# 03-DRAM_Memory.net
KiCad netlist of a schematic drawn in Altium Designer
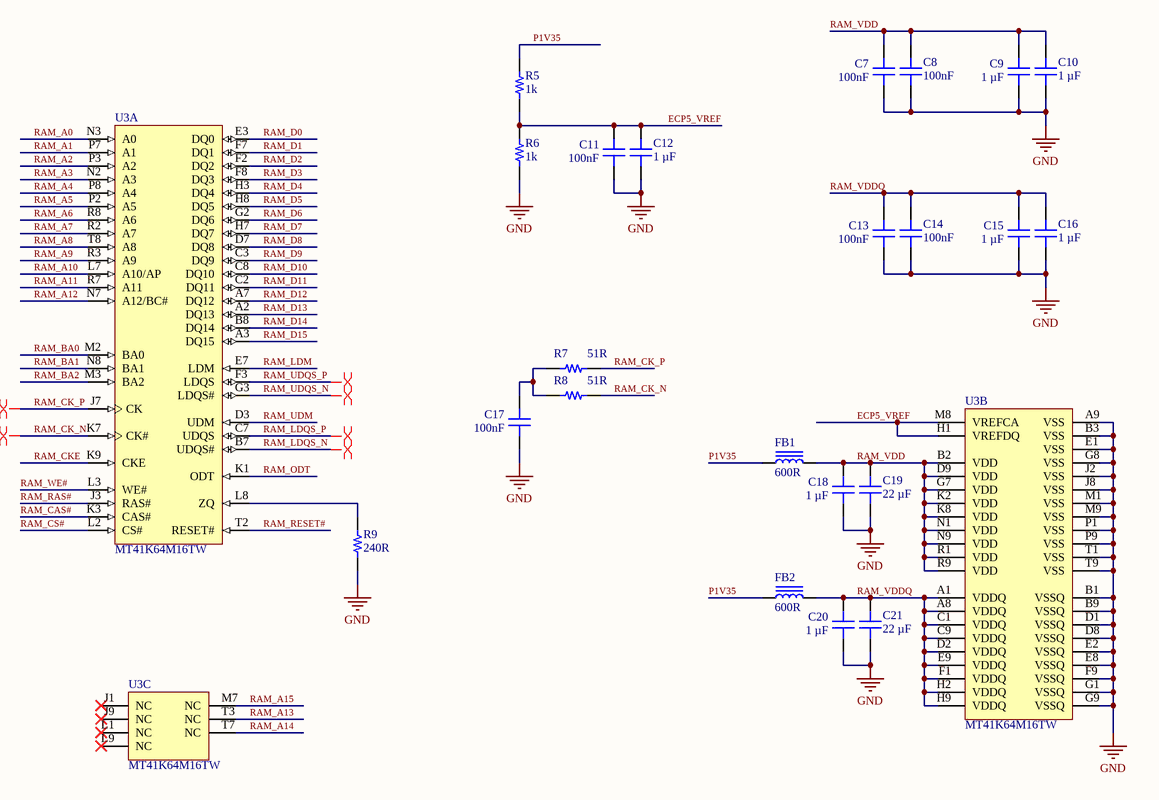
[diagram p0: 03-DRAM_Memory.SchDoc]

(export (version "E")
  (design (tool "Eeschema 10.0.6"))
  (components
    (comp (ref "C7")
      (value "100nF")
      (footprint "CAP 0201_0603")
      (description "CAP CER 0.1UF 6.3V X6S 0201")
      (fields
        (field (name "PART NUMBER") "GRT033C80J104KE01J")
        (field (name "MANUFACTURER") "Murata Electronics")
        (field (name "LASTUPDATED") "3/01/2023 8:00:58 p. m.")
      )
      (libsource (lib "Celestial Altium Library - altium_library") (part "Capacitor"))
    )
    (comp (ref "C8")
      (value "100nF")
      (footprint "CAP 0201_0603")
      (description "CAP CER 0.1UF 6.3V X6S 0201")
      (fields
        (field (name "PART NUMBER") "GRT033C80J104KE01J")
        (field (name "MANUFACTURER") "Murata Electronics")
        (field (name "LASTUPDATED") "3/01/2023 8:00:58 p. m.")
      )
      (libsource (lib "Celestial Altium Library - altium_library") (part "Capacitor"))
    )
    (comp (ref "C9")
      (value "1 µF")
      (footprint "CAP 0402_1005")
      (description "CAP CER 1UF 10V X6S 0402")
      (fields
        (field (name "PART NUMBER") "LMK105C6105KV-F")
        (field (name "MANUFACTURER") "Taiyo Yuden")
        (field (name "LASTUPDATED") "3/01/2023 8:04:17 p. m.")
      )
      (libsource (lib "Celestial Altium Library - altium_library") (part "Capacitor"))
    )
    (comp (ref "C10")
      (value "1 µF")
      (footprint "CAP 0402_1005")
      (description "CAP CER 1UF 10V X6S 0402")
      (fields
        (field (name "PART NUMBER") "LMK105C6105KV-F")
        (field (name "MANUFACTURER") "Taiyo Yuden")
        (field (name "LASTUPDATED") "3/01/2023 8:04:17 p. m.")
      )
      (libsource (lib "Celestial Altium Library - altium_library") (part "Capacitor"))
    )
    (comp (ref "C11")
      (value "100nF")
      (footprint "CAP 0201_0603")
      (description "CAP CER 0.1UF 6.3V X6S 0201")
      (fields
        (field (name "PART NUMBER") "GRT033C80J104KE01J")
        (field (name "MANUFACTURER") "Murata Electronics")
        (field (name "LASTUPDATED") "3/01/2023 8:00:58 p. m.")
      )
      (libsource (lib "Celestial Altium Library - altium_library") (part "Capacitor"))
    )
    (comp (ref "C12")
      (value "1 µF")
      (footprint "CAP 0402_1005")
      (description "CAP CER 1UF 10V X6S 0402")
      (fields
        (field (name "PART NUMBER") "LMK105C6105KV-F")
        (field (name "MANUFACTURER") "Taiyo Yuden")
        (field (name "LASTUPDATED") "3/01/2023 8:04:17 p. m.")
      )
      (libsource (lib "Celestial Altium Library - altium_library") (part "Capacitor"))
    )
    (comp (ref "C13")
      (value "100nF")
      (footprint "CAP 0201_0603")
      (description "CAP CER 0.1UF 6.3V X6S 0201")
      (fields
        (field (name "PART NUMBER") "GRT033C80J104KE01J")
        (field (name "MANUFACTURER") "Murata Electronics")
        (field (name "LASTUPDATED") "3/01/2023 8:00:58 p. m.")
      )
      (libsource (lib "Celestial Altium Library - altium_library") (part "Capacitor"))
    )
    (comp (ref "C14")
      (value "100nF")
      (footprint "CAP 0201_0603")
      (description "CAP CER 0.1UF 6.3V X6S 0201")
      (fields
        (field (name "PART NUMBER") "GRT033C80J104KE01J")
        (field (name "MANUFACTURER") "Murata Electronics")
        (field (name "LASTUPDATED") "3/01/2023 8:00:58 p. m.")
      )
      (libsource (lib "Celestial Altium Library - altium_library") (part "Capacitor"))
    )
    (comp (ref "C15")
      (value "1 µF")
      (footprint "CAP 0402_1005")
      (description "CAP CER 1UF 10V X6S 0402")
      (fields
        (field (name "PART NUMBER") "LMK105C6105KV-F")
        (field (name "MANUFACTURER") "Taiyo Yuden")
        (field (name "LASTUPDATED") "3/01/2023 8:04:17 p. m.")
      )
      (libsource (lib "Celestial Altium Library - altium_library") (part "Capacitor"))
    )
    (comp (ref "C16")
      (value "1 µF")
      (footprint "CAP 0402_1005")
      (description "CAP CER 1UF 10V X6S 0402")
      (fields
        (field (name "PART NUMBER") "LMK105C6105KV-F")
        (field (name "MANUFACTURER") "Taiyo Yuden")
        (field (name "LASTUPDATED") "3/01/2023 8:04:17 p. m.")
      )
      (libsource (lib "Celestial Altium Library - altium_library") (part "Capacitor"))
    )
    (comp (ref "C17")
      (value "100nF")
      (footprint "CAP 0201_0603")
      (description "CAP CER 0.1UF 6.3V X6S 0201")
      (fields
        (field (name "PART NUMBER") "GRT033C80J104KE01J")
        (field (name "MANUFACTURER") "Murata Electronics")
        (field (name "LASTUPDATED") "3/01/2023 8:00:58 p. m.")
      )
      (libsource (lib "Celestial Altium Library - altium_library") (part "Capacitor"))
    )
    (comp (ref "C18")
      (value "1 µF")
      (footprint "CAP 0402_1005")
      (description "CAP CER 1UF 10V X6S 0402")
      (fields
        (field (name "PART NUMBER") "LMK105C6105KV-F")
        (field (name "MANUFACTURER") "Taiyo Yuden")
        (field (name "LASTUPDATED") "3/01/2023 8:04:17 p. m.")
      )
      (libsource (lib "Celestial Altium Library - altium_library") (part "Capacitor"))
    )
    (comp (ref "C19")
      (value "22 µF")
      (footprint "CAP 0603_1608")
      (description "CAP CER 22UF 6.3V X5R 0603")
      (fields
        (field (name "PART NUMBER") "GRM186R60J226ME15D")
        (field (name "MANUFACTURER") "Murata Electronics")
        (field (name "LASTUPDATED") "3/01/2023 8:07:48 p. m.")
      )
      (libsource (lib "Celestial Altium Library - altium_library") (part "Capacitor"))
    )
    (comp (ref "C20")
      (value "1 µF")
      (footprint "CAP 0402_1005")
      (description "CAP CER 1UF 10V X6S 0402")
      (fields
        (field (name "PART NUMBER") "LMK105C6105KV-F")
        (field (name "MANUFACTURER") "Taiyo Yuden")
        (field (name "LASTUPDATED") "3/01/2023 8:04:17 p. m.")
      )
      (libsource (lib "Celestial Altium Library - altium_library") (part "Capacitor"))
    )
    (comp (ref "C21")
      (value "22 µF")
      (footprint "CAP 0603_1608")
      (description "CAP CER 22UF 6.3V X5R 0603")
      (fields
        (field (name "PART NUMBER") "GRM186R60J226ME15D")
        (field (name "MANUFACTURER") "Murata Electronics")
        (field (name "LASTUPDATED") "3/01/2023 8:07:48 p. m.")
      )
      (libsource (lib "Celestial Altium Library - altium_library") (part "Capacitor"))
    )
    (comp (ref "FB1")
      (value "600R")
      (footprint "IND 0402_1005 RF WW")
      (description "FIXED IND 4.8NH 1.2A 71MOHM SMD")
      (fields
        (field (name "PART NUMBER") "LQW15AN4N8D8ZD")
        (field (name "MANUFACTURER") "Murata Electronics")
        (field (name "LASTUPDATED") "2/01/2023 8:59:34 p. m.")
      )
      (libsource (lib "Celestial Altium Library - altium_library") (part "Inductor"))
    )
    (comp (ref "FB2")
      (value "600R")
      (footprint "IND 0402_1005 RF WW")
      (description "FIXED IND 4.8NH 1.2A 71MOHM SMD")
      (fields
        (field (name "PART NUMBER") "LQW15AN4N8D8ZD")
        (field (name "MANUFACTURER") "Murata Electronics")
        (field (name "LASTUPDATED") "2/01/2023 8:59:34 p. m.")
      )
      (libsource (lib "Celestial Altium Library - altium_library") (part "Inductor"))
    )
    (comp (ref "R5")
      (value "1k")
      (footprint "RES 0201_0603")
      (description "RES SMD 10K OHM 0.1% 1/20W 0201")
      (fields
        (field (name "PART NUMBER") "ERA-1AEB103C")
        (field (name "MANUFACTURER") "Panasonic Electronic Components")
        (field (name "LASTUPDATED") "3/01/2023 8:15:23 p. m.")
      )
      (libsource (lib "Celestial Altium Library - altium_library") (part "Resistor"))
    )
    (comp (ref "R6")
      (value "1k")
      (footprint "RES 0201_0603")
      (description "RES SMD 10K OHM 0.1% 1/20W 0201")
      (fields
        (field (name "PART NUMBER") "ERA-1AEB103C")
        (field (name "MANUFACTURER") "Panasonic Electronic Components")
        (field (name "LASTUPDATED") "3/01/2023 8:15:23 p. m.")
      )
      (libsource (lib "Celestial Altium Library - altium_library") (part "Resistor"))
    )
    (comp (ref "R7")
      (value "51R")
      (footprint "RES 0201_0603")
      (description "RES SMD 10K OHM 0.1% 1/20W 0201")
      (fields
        (field (name "PART NUMBER") "ERA-1AEB103C")
        (field (name "MANUFACTURER") "Panasonic Electronic Components")
        (field (name "LASTUPDATED") "3/01/2023 8:15:23 p. m.")
      )
      (libsource (lib "Celestial Altium Library - altium_library") (part "Resistor"))
    )
    (comp (ref "R8")
      (value "51R")
      (footprint "RES 0201_0603")
      (description "RES SMD 10K OHM 0.1% 1/20W 0201")
      (fields
        (field (name "PART NUMBER") "ERA-1AEB103C")
        (field (name "MANUFACTURER") "Panasonic Electronic Components")
        (field (name "LASTUPDATED") "3/01/2023 8:15:23 p. m.")
      )
      (libsource (lib "Celestial Altium Library - altium_library") (part "Resistor"))
    )
    (comp (ref "R9")
      (value "240R")
      (footprint "RES 0402_1005")
      (description "RES SMD 124 OHM 1% 1/10W 0402")
      (fields
        (field (name "PART NUMBER") "ERJ-2RKF1240X")
        (field (name "MANUFACTURER") "Panasonic Electronic Components")
        (field (name "LASTUPDATED") "2/01/2023 8:21:47 p. m.")
      )
      (libsource (lib "Celestial Altium Library - altium_library") (part "Resistor"))
    )
    (comp (ref "U3")
      (value "MT41K64M16TW")
      (footprint "MICT-TW-96")
      (description "DDR3L SDRAM, 8 Meg x 16 x 8 Bank, 1.07 ns, 0 to 95 degC, 96-Ball FBGA (TW), Pb-Free")
      (libsource (lib "MT41K64M16TW") (part "MT41K64M16TW"))
    )
  )
  (nets
    (net (code "1") (name "/ECP5_VREF") (class "Default")
      (node (ref "C11") (pin "2") (pinfunction "2_2") (pintype "passive"))
      (node (ref "C12") (pin "2") (pinfunction "2_2") (pintype "passive"))
      (node (ref "R5") (pin "2") (pinfunction "2_2") (pintype "passive"))
      (node (ref "R6") (pin "1") (pinfunction "1_1") (pintype "passive"))
      (node (ref "U3") (pin "H1") (pinfunction "VREFDQ_H1") (pintype "power_in"))
      (node (ref "U3") (pin "M8") (pinfunction "VREFCA_M8") (pintype "power_in"))
    )
    (net (code "2") (name "/P1V35") (class "Default")
      (node (ref "FB1") (pin "1") (pinfunction "1_1") (pintype "passive"))
      (node (ref "FB2") (pin "1") (pinfunction "1_1") (pintype "passive"))
      (node (ref "R5") (pin "1") (pinfunction "1_1") (pintype "passive"))
    )
    (net (code "3") (name "/RAM_A0") (class "Default")
      (node (ref "U3") (pin "N3") (pinfunction "A0_N3") (pintype "input"))
    )
    (net (code "4") (name "/RAM_A1") (class "Default")
      (node (ref "U3") (pin "P7") (pinfunction "A1_P7") (pintype "input"))
    )
    (net (code "5") (name "/RAM_A2") (class "Default")
      (node (ref "U3") (pin "P3") (pinfunction "A2_P3") (pintype "input"))
    )
    (net (code "6") (name "/RAM_A3") (class "Default")
      (node (ref "U3") (pin "N2") (pinfunction "A3_N2") (pintype "input"))
    )
    (net (code "7") (name "/RAM_A4") (class "Default")
      (node (ref "U3") (pin "P8") (pinfunction "A4_P8") (pintype "input"))
    )
    (net (code "8") (name "/RAM_A5") (class "Default")
      (node (ref "U3") (pin "P2") (pinfunction "A5_P2") (pintype "input"))
    )
    (net (code "9") (name "/RAM_A6") (class "Default")
      (node (ref "U3") (pin "R8") (pinfunction "A6_R8") (pintype "input"))
    )
    (net (code "10") (name "/RAM_A7") (class "Default")
      (node (ref "U3") (pin "R2") (pinfunction "A7_R2") (pintype "input"))
    )
    (net (code "11") (name "/RAM_A8") (class "Default")
      (node (ref "U3") (pin "T8") (pinfunction "A8_T8") (pintype "input"))
    )
    (net (code "12") (name "/RAM_A9") (class "Default")
      (node (ref "U3") (pin "R3") (pinfunction "A9_R3") (pintype "input"))
    )
    (net (code "13") (name "/RAM_A10") (class "Default")
      (node (ref "U3") (pin "L7") (pinfunction "A10/AP_L7") (pintype "input"))
    )
    (net (code "14") (name "/RAM_A11") (class "Default")
      (node (ref "U3") (pin "R7") (pinfunction "A11_R7") (pintype "input"))
    )
    (net (code "15") (name "/RAM_A12") (class "Default")
      (node (ref "U3") (pin "N7") (pinfunction "A12/BC#_N7") (pintype "input"))
    )
    (net (code "16") (name "/RAM_A13") (class "Default")
      (node (ref "U3") (pin "T3") (pinfunction "NC_T3") (pintype "passive"))
    )
    (net (code "17") (name "/RAM_A14") (class "Default")
      (node (ref "U3") (pin "T7") (pinfunction "NC_T7") (pintype "passive"))
    )
    (net (code "18") (name "/RAM_A15") (class "Default")
      (node (ref "U3") (pin "M7") (pinfunction "NC_M7") (pintype "passive"))
    )
    (net (code "19") (name "/RAM_BA0") (class "Default")
      (node (ref "U3") (pin "M2") (pinfunction "BA0_M2") (pintype "input"))
    )
    (net (code "20") (name "/RAM_BA1") (class "Default")
      (node (ref "U3") (pin "N8") (pinfunction "BA1_N8") (pintype "input"))
    )
    (net (code "21") (name "/RAM_BA2") (class "Default")
      (node (ref "U3") (pin "M3") (pinfunction "BA2_M3") (pintype "input"))
    )
    (net (code "22") (name "/RAM_CAS#") (class "Default")
      (node (ref "U3") (pin "K3") (pinfunction "CAS#_K3") (pintype "input"))
    )
    (net (code "23") (name "/RAM_CKE") (class "Default")
      (node (ref "U3") (pin "K9") (pinfunction "CKE_K9") (pintype "input"))
    )
    (net (code "24") (name "/RAM_CK_N") (class "Default")
      (node (ref "R8") (pin "2") (pinfunction "2_2") (pintype "passive"))
      (node (ref "U3") (pin "K7") (pinfunction "CK#_K7") (pintype "input"))
    )
    (net (code "25") (name "/RAM_CK_P") (class "Default")
      (node (ref "R7") (pin "2") (pinfunction "2_2") (pintype "passive"))
      (node (ref "U3") (pin "J7") (pinfunction "CK_J7") (pintype "input"))
    )
    (net (code "26") (name "/RAM_CS#") (class "Default")
      (node (ref "U3") (pin "L2") (pinfunction "CS#_L2") (pintype "input"))
    )
    (net (code "27") (name "/RAM_D0") (class "Default")
      (node (ref "U3") (pin "E3") (pinfunction "DQ0_E3") (pintype "bidirectional"))
    )
    (net (code "28") (name "/RAM_D1") (class "Default")
      (node (ref "U3") (pin "F7") (pinfunction "DQ1_F7") (pintype "bidirectional"))
    )
    (net (code "29") (name "/RAM_D2") (class "Default")
      (node (ref "U3") (pin "F2") (pinfunction "DQ2_F2") (pintype "bidirectional"))
    )
    (net (code "30") (name "/RAM_D3") (class "Default")
      (node (ref "U3") (pin "F8") (pinfunction "DQ3_F8") (pintype "bidirectional"))
    )
    (net (code "31") (name "/RAM_D4") (class "Default")
      (node (ref "U3") (pin "H3") (pinfunction "DQ4_H3") (pintype "bidirectional"))
    )
    (net (code "32") (name "/RAM_D5") (class "Default")
      (node (ref "U3") (pin "H8") (pinfunction "DQ5_H8") (pintype "bidirectional"))
    )
    (net (code "33") (name "/RAM_D6") (class "Default")
      (node (ref "U3") (pin "G2") (pinfunction "DQ6_G2") (pintype "bidirectional"))
    )
    (net (code "34") (name "/RAM_D7") (class "Default")
      (node (ref "U3") (pin "H7") (pinfunction "DQ7_H7") (pintype "bidirectional"))
    )
    (net (code "35") (name "/RAM_D8") (class "Default")
      (node (ref "U3") (pin "D7") (pinfunction "DQ8_D7") (pintype "bidirectional"))
    )
    (net (code "36") (name "/RAM_D9") (class "Default")
      (node (ref "U3") (pin "C3") (pinfunction "DQ9_C3") (pintype "bidirectional"))
    )
    (net (code "37") (name "/RAM_D10") (class "Default")
      (node (ref "U3") (pin "C8") (pinfunction "DQ10_C8") (pintype "bidirectional"))
    )
    (net (code "38") (name "/RAM_D11") (class "Default")
      (node (ref "U3") (pin "C2") (pinfunction "DQ11_C2") (pintype "bidirectional"))
    )
    (net (code "39") (name "/RAM_D12") (class "Default")
      (node (ref "U3") (pin "A7") (pinfunction "DQ12_A7") (pintype "bidirectional"))
    )
    (net (code "40") (name "/RAM_D13") (class "Default")
      (node (ref "U3") (pin "A2") (pinfunction "DQ13_A2") (pintype "bidirectional"))
    )
    (net (code "41") (name "/RAM_D14") (class "Default")
      (node (ref "U3") (pin "B8") (pinfunction "DQ14_B8") (pintype "bidirectional"))
    )
    (net (code "42") (name "/RAM_D15") (class "Default")
      (node (ref "U3") (pin "A3") (pinfunction "DQ15_A3") (pintype "bidirectional"))
    )
    (net (code "43") (name "/RAM_LDM") (class "Default")
      (node (ref "U3") (pin "E7") (pinfunction "LDM_E7") (pintype "input"))
    )
    (net (code "44") (name "/RAM_LDQS_N") (class "Default")
      (node (ref "U3") (pin "B7") (pinfunction "UDQS#_B7") (pintype "bidirectional"))
    )
    (net (code "45") (name "/RAM_LDQS_P") (class "Default")
      (node (ref "U3") (pin "C7") (pinfunction "UDQS_C7") (pintype "bidirectional"))
    )
    (net (code "46") (name "/RAM_ODT") (class "Default")
      (node (ref "U3") (pin "K1") (pinfunction "ODT_K1") (pintype "input"))
    )
    (net (code "47") (name "/RAM_RAS#") (class "Default")
      (node (ref "U3") (pin "J3") (pinfunction "RAS#_J3") (pintype "input"))
    )
    (net (code "48") (name "/RAM_RESET#") (class "Default")
      (node (ref "U3") (pin "T2") (pinfunction "RESET#_T2") (pintype "input"))
    )
    (net (code "49") (name "/RAM_UDM") (class "Default")
      (node (ref "U3") (pin "D3") (pinfunction "UDM_D3") (pintype "input"))
    )
    (net (code "50") (name "/RAM_UDQS_N") (class "Default")
      (node (ref "U3") (pin "G3") (pinfunction "LDQS#_G3") (pintype "bidirectional"))
    )
    (net (code "51") (name "/RAM_UDQS_P") (class "Default")
      (node (ref "U3") (pin "F3") (pinfunction "LDQS_F3") (pintype "bidirectional"))
    )
    (net (code "52") (name "/RAM_VDD") (class "Default")
      (node (ref "C10") (pin "2") (pinfunction "2_2") (pintype "passive"))
      (node (ref "C18") (pin "2") (pinfunction "2_2") (pintype "passive"))
      (node (ref "C19") (pin "2") (pinfunction "2_2") (pintype "passive"))
      (node (ref "C7") (pin "2") (pinfunction "2_2") (pintype "passive"))
      (node (ref "C8") (pin "2") (pinfunction "2_2") (pintype "passive"))
      (node (ref "C9") (pin "2") (pinfunction "2_2") (pintype "passive"))
      (node (ref "FB1") (pin "2") (pinfunction "2_2") (pintype "passive"))
      (node (ref "U3") (pin "B2") (pinfunction "VDD_B2") (pintype "power_in"))
      (node (ref "U3") (pin "D9") (pinfunction "VDD_D9") (pintype "power_in"))
      (node (ref "U3") (pin "G7") (pinfunction "VDD_G7") (pintype "power_in"))
      (node (ref "U3") (pin "K2") (pinfunction "VDD_K2") (pintype "power_in"))
      (node (ref "U3") (pin "K8") (pinfunction "VDD_K8") (pintype "power_in"))
      (node (ref "U3") (pin "N1") (pinfunction "VDD_N1") (pintype "power_in"))
      (node (ref "U3") (pin "N9") (pinfunction "VDD_N9") (pintype "power_in"))
      (node (ref "U3") (pin "R1") (pinfunction "VDD_R1") (pintype "power_in"))
      (node (ref "U3") (pin "R9") (pinfunction "VDD_R9") (pintype "power_in"))
    )
    (net (code "53") (name "/RAM_VDDQ") (class "Default")
      (node (ref "C13") (pin "2") (pinfunction "2_2") (pintype "passive"))
      (node (ref "C14") (pin "2") (pinfunction "2_2") (pintype "passive"))
      (node (ref "C15") (pin "2") (pinfunction "2_2") (pintype "passive"))
      (node (ref "C16") (pin "2") (pinfunction "2_2") (pintype "passive"))
      (node (ref "C20") (pin "2") (pinfunction "2_2") (pintype "passive"))
      (node (ref "C21") (pin "2") (pinfunction "2_2") (pintype "passive"))
      (node (ref "FB2") (pin "2") (pinfunction "2_2") (pintype "passive"))
      (node (ref "U3") (pin "A1") (pinfunction "VDDQ_A1") (pintype "power_in"))
      (node (ref "U3") (pin "A8") (pinfunction "VDDQ_A8") (pintype "power_in"))
      (node (ref "U3") (pin "C1") (pinfunction "VDDQ_C1") (pintype "power_in"))
      (node (ref "U3") (pin "C9") (pinfunction "VDDQ_C9") (pintype "power_in"))
      (node (ref "U3") (pin "D2") (pinfunction "VDDQ_D2") (pintype "power_in"))
      (node (ref "U3") (pin "E9") (pinfunction "VDDQ_E9") (pintype "power_in"))
      (node (ref "U3") (pin "F1") (pinfunction "VDDQ_F1") (pintype "power_in"))
      (node (ref "U3") (pin "H2") (pinfunction "VDDQ_H2") (pintype "power_in"))
      (node (ref "U3") (pin "H9") (pinfunction "VDDQ_H9") (pintype "power_in"))
    )
    (net (code "54") (name "/RAM_WE#") (class "Default")
      (node (ref "U3") (pin "L3") (pinfunction "WE#_L3") (pintype "input"))
    )
    (net (code "55") (name "GND") (class "Default")
      (node (ref "C10") (pin "1") (pinfunction "1_1") (pintype "passive"))
      (node (ref "C11") (pin "1") (pinfunction "1_1") (pintype "passive"))
      (node (ref "C12") (pin "1") (pinfunction "1_1") (pintype "passive"))
      (node (ref "C13") (pin "1") (pinfunction "1_1") (pintype "passive"))
      (node (ref "C14") (pin "1") (pinfunction "1_1") (pintype "passive"))
      (node (ref "C15") (pin "1") (pinfunction "1_1") (pintype "passive"))
      (node (ref "C16") (pin "1") (pinfunction "1_1") (pintype "passive"))
      (node (ref "C17") (pin "1") (pinfunction "1_1") (pintype "passive"))
      (node (ref "C18") (pin "1") (pinfunction "1_1") (pintype "passive"))
      (node (ref "C19") (pin "1") (pinfunction "1_1") (pintype "passive"))
      (node (ref "C20") (pin "1") (pinfunction "1_1") (pintype "passive"))
      (node (ref "C21") (pin "1") (pinfunction "1_1") (pintype "passive"))
      (node (ref "C7") (pin "1") (pinfunction "1_1") (pintype "passive"))
      (node (ref "C8") (pin "1") (pinfunction "1_1") (pintype "passive"))
      (node (ref "C9") (pin "1") (pinfunction "1_1") (pintype "passive"))
      (node (ref "R6") (pin "2") (pinfunction "2_2") (pintype "passive"))
      (node (ref "R9") (pin "1") (pinfunction "1_1") (pintype "passive"))
      (node (ref "U3") (pin "A9") (pinfunction "VSS_A9") (pintype "power_in"))
      (node (ref "U3") (pin "B1") (pinfunction "VSSQ_B1") (pintype "power_in"))
      (node (ref "U3") (pin "B3") (pinfunction "VSS_B3") (pintype "power_in"))
      (node (ref "U3") (pin "B9") (pinfunction "VSSQ_B9") (pintype "power_in"))
      (node (ref "U3") (pin "D1") (pinfunction "VSSQ_D1") (pintype "power_in"))
      (node (ref "U3") (pin "D8") (pinfunction "VSSQ_D8") (pintype "power_in"))
      (node (ref "U3") (pin "E1") (pinfunction "VSS_E1") (pintype "power_in"))
      (node (ref "U3") (pin "E2") (pinfunction "VSSQ_E2") (pintype "power_in"))
      (node (ref "U3") (pin "E8") (pinfunction "VSSQ_E8") (pintype "power_in"))
      (node (ref "U3") (pin "F9") (pinfunction "VSSQ_F9") (pintype "power_in"))
      (node (ref "U3") (pin "G1") (pinfunction "VSSQ_G1") (pintype "power_in"))
      (node (ref "U3") (pin "G8") (pinfunction "VSS_G8") (pintype "power_in"))
      (node (ref "U3") (pin "G9") (pinfunction "VSSQ_G9") (pintype "power_in"))
      (node (ref "U3") (pin "J2") (pinfunction "VSS_J2") (pintype "power_in"))
      (node (ref "U3") (pin "J8") (pinfunction "VSS_J8") (pintype "power_in"))
      (node (ref "U3") (pin "M1") (pinfunction "VSS_M1") (pintype "power_in"))
      (node (ref "U3") (pin "M9") (pinfunction "VSS_M9") (pintype "power_in"))
      (node (ref "U3") (pin "P1") (pinfunction "VSS_P1") (pintype "power_in"))
      (node (ref "U3") (pin "P9") (pinfunction "VSS_P9") (pintype "power_in"))
      (node (ref "U3") (pin "T1") (pinfunction "VSS_T1") (pintype "power_in"))
      (node (ref "U3") (pin "T9") (pinfunction "VSS_T9") (pintype "power_in"))
    )
    (net (code "56") (name "Net-(C17-Pad2)") (class "Default")
      (node (ref "C17") (pin "2") (pinfunction "2_2") (pintype "passive"))
      (node (ref "R7") (pin "1") (pinfunction "1_1") (pintype "passive"))
      (node (ref "R8") (pin "1") (pinfunction "1_1") (pintype "passive"))
    )
    (net (code "57") (name "Net-(U3A-ZQ)") (class "Default")
      (node (ref "R9") (pin "2") (pinfunction "2_2") (pintype "passive"))
      (node (ref "U3") (pin "L8") (pinfunction "ZQ_L8") (pintype "input"))
    )
    (net (code "58") (name "unconnected-(U3C-NC-PadJ1)") (class "Default")
      (node (ref "U3") (pin "J1") (pinfunction "NC_J1") (pintype "passive+no_connect"))
    )
    (net (code "59") (name "unconnected-(U3C-NC-PadJ9)") (class "Default")
      (node (ref "U3") (pin "J9") (pinfunction "NC_J9") (pintype "passive+no_connect"))
    )
    (net (code "60") (name "unconnected-(U3C-NC-PadL1)") (class "Default")
      (node (ref "U3") (pin "L1") (pinfunction "NC_L1") (pintype "passive+no_connect"))
    )
    (net (code "61") (name "unconnected-(U3C-NC-PadL9)") (class "Default")
      (node (ref "U3") (pin "L9") (pinfunction "NC_L9") (pintype "passive+no_connect"))
    )
  )
)
